# SCH_n2_power_distribution_board_v3_2022-.net
KiCad netlist of a schematic drawn in EasyEDA
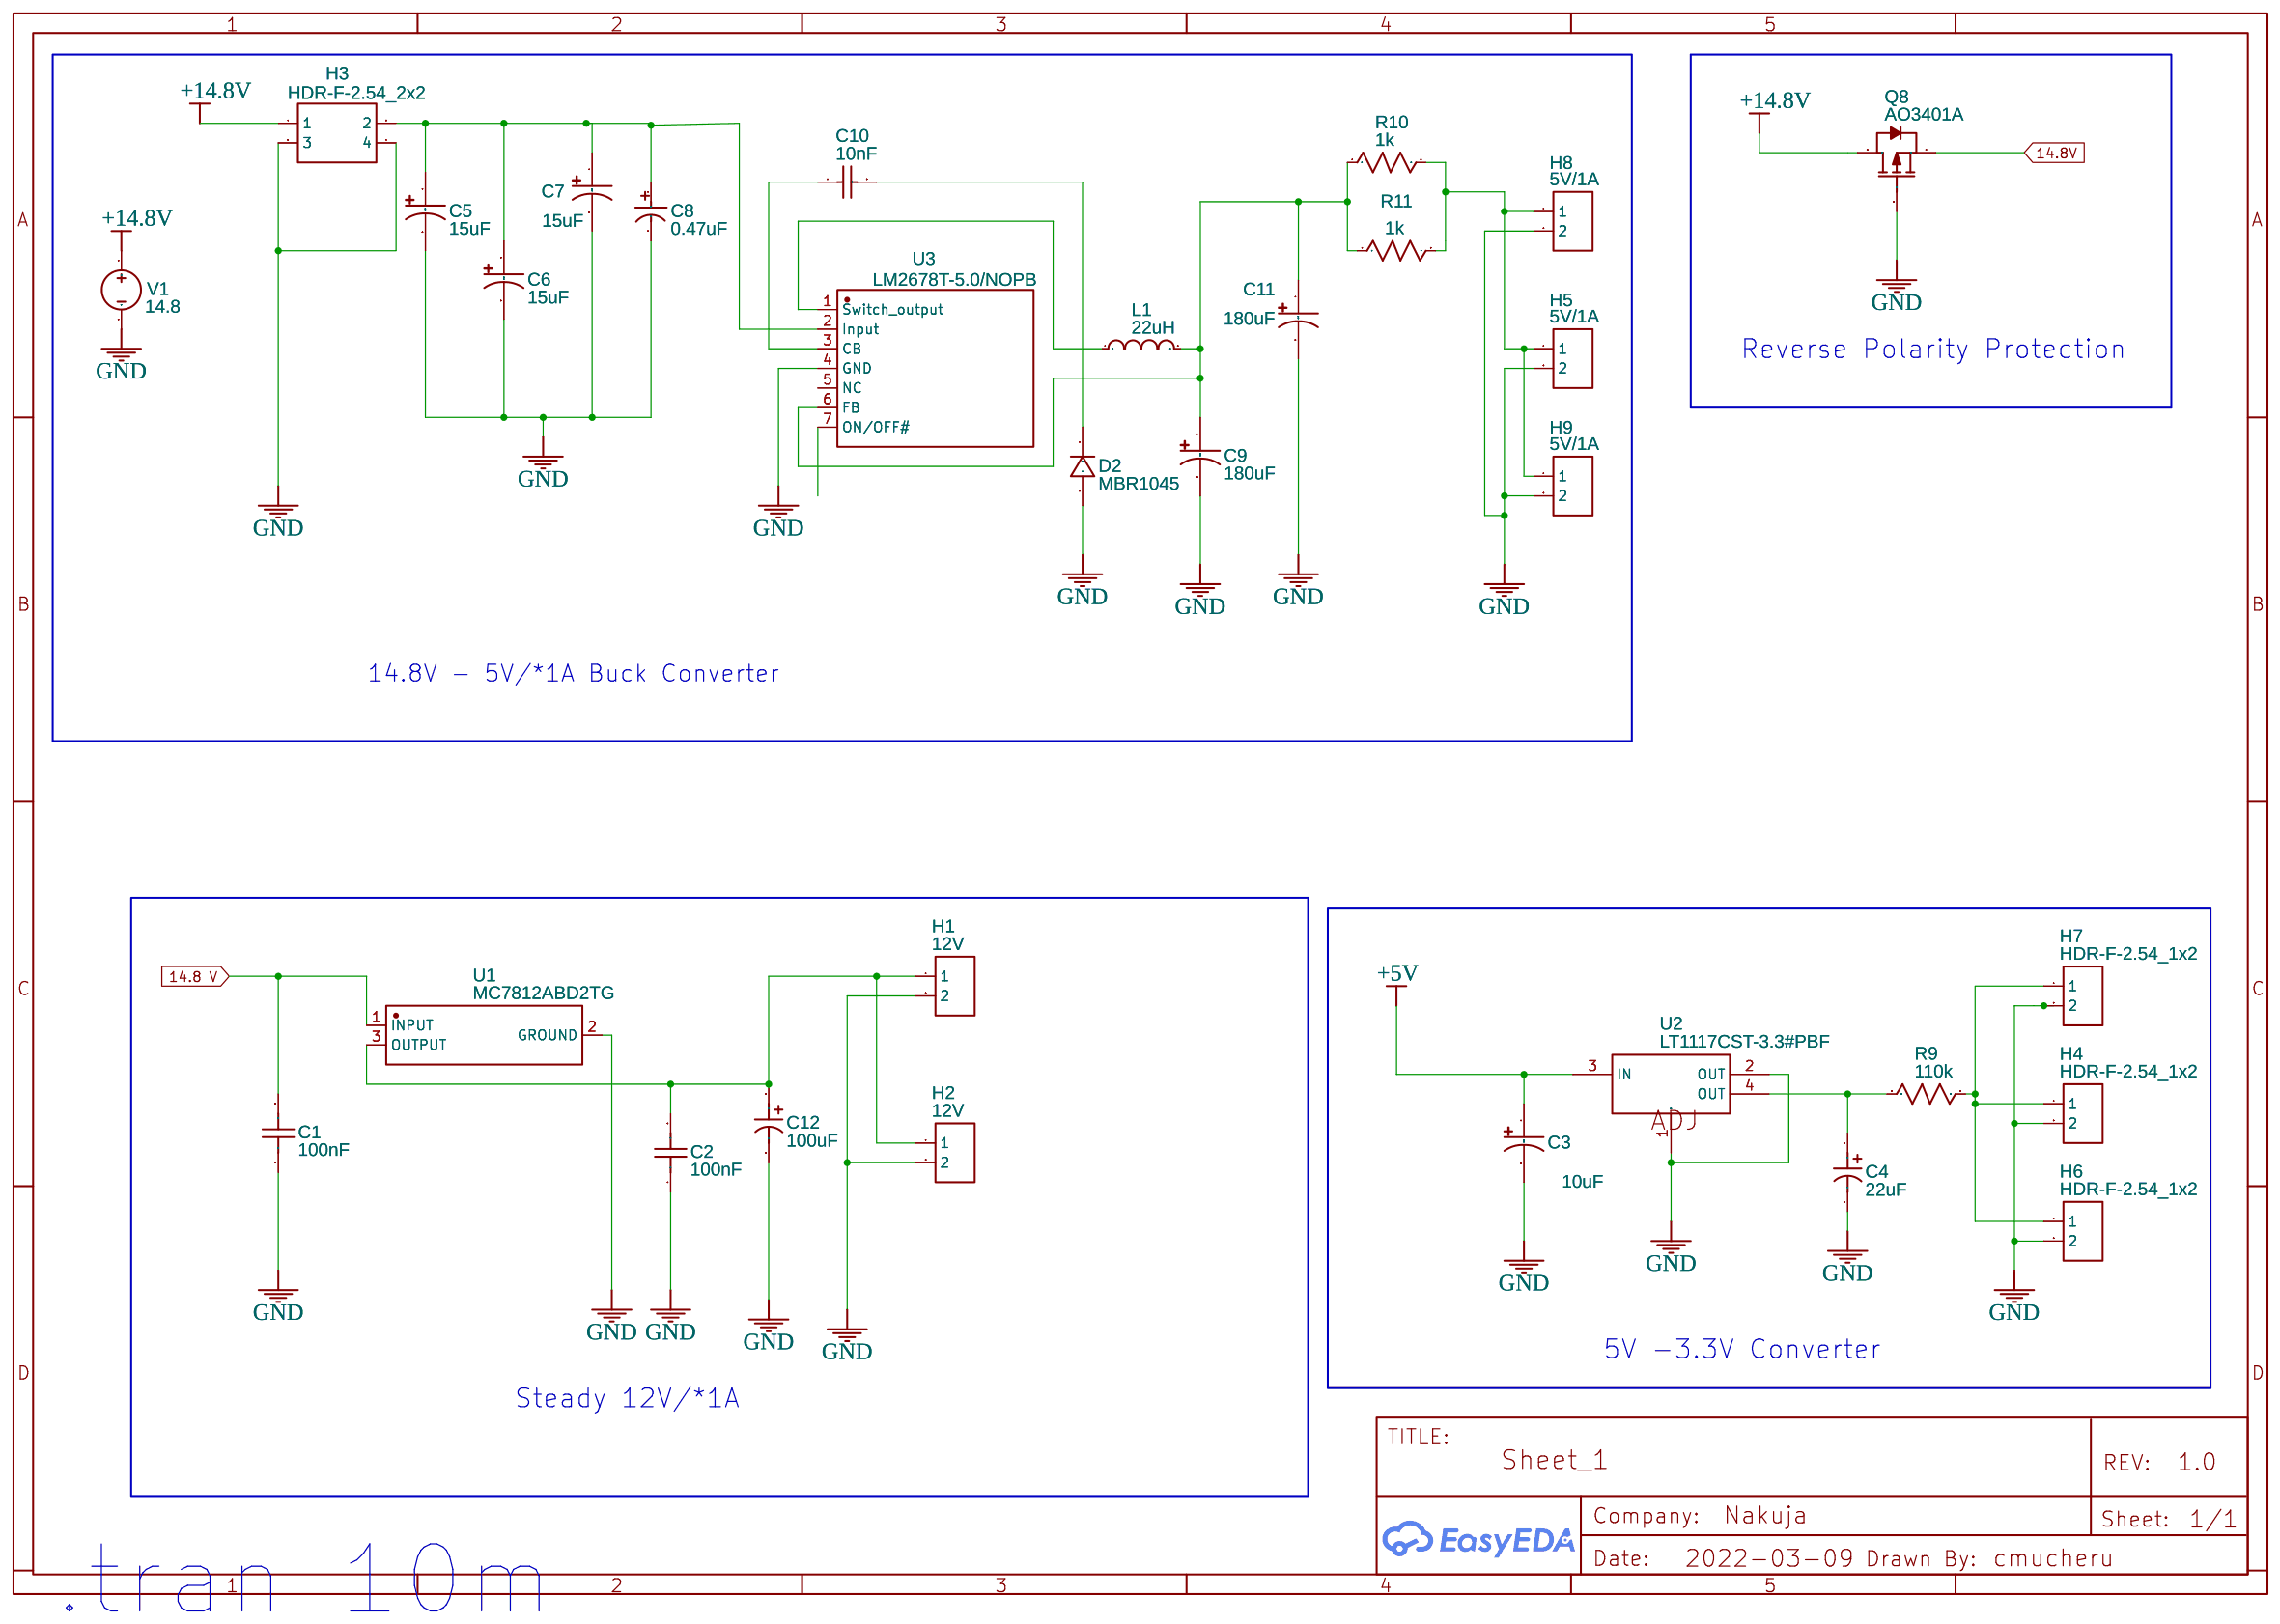
[diagram p0: schematic sheet]

(export (version "E")
  (design (tool "Eeschema 10.0.6"))
  (components
    (comp (ref "C1")
      (value "100nF")
      (fields
        (field (name "BOM_Manufacturer Part") "CC1H104ZA19D3F5P10MF")
        (field (name "BOM_Supplier Part") "C254086")
      )
      (libsource (lib "") (part "CC1H104ZA19D3F5P10MF"))
    )
    (comp (ref "C2")
      (value "100nF")
      (fields
        (field (name "BOM_Manufacturer Part") "CC1H104ZA19D3F5P10MF")
        (field (name "BOM_Supplier Part") "C254086")
      )
      (libsource (lib "") (part "CC1H104ZA19D3F5P10MF"))
    )
    (comp (ref "C3")
      (value "10uF")
      (fields
        (field (name "BOM_Manufacturer Part") "VE-100M1H0505-TRO")
        (field (name "BOM_Supplier Part") "C249452")
      )
      (libsource (lib "") (part "VE-100M1H0505-TRO"))
    )
    (comp (ref "C4")
      (value "22uF")
      (fields
        (field (name "BOM_Manufacturer Part") "RVT22UF50V67RV0028")
        (field (name "BOM_Supplier Part") "C2836438")
      )
      (libsource (lib "") (part "RVT22UF50V67RV0028"))
    )
    (comp (ref "C5")
      (value "15uF")
      (fields
        (field (name "BOM_Manufacturer Part") "UUD1H150MCL1GS")
        (field (name "BOM_Supplier Part") "C340748")
      )
      (libsource (lib "") (part "UUD1H150MCL1GS"))
    )
    (comp (ref "C6")
      (value "15uF")
      (fields
        (field (name "BOM_Manufacturer Part") "UUD1H150MCL1GS")
        (field (name "BOM_Supplier Part") "C340748")
      )
      (libsource (lib "") (part "UUD1H150MCL1GS"))
    )
    (comp (ref "C7")
      (value "15uF")
      (fields
        (field (name "BOM_Manufacturer Part") "UUD1H150MCL1GS")
        (field (name "BOM_Supplier Part") "C340748")
      )
      (libsource (lib "") (part "UUD1H150MCL1GS_1"))
    )
    (comp (ref "C8")
      (value "0.47uF")
      (fields
        (field (name "BOM_Manufacturer Part") "CS1HR47M-CRC54")
        (field (name "BOM_Supplier Part") "C117834")
      )
      (libsource (lib "") (part "CS1HR47M-CRC54"))
    )
    (comp (ref "C9")
      (value "180uF")
      (fields
        (field (name "BOM_Manufacturer Part") "VKMC1001C181MV")
        (field (name "BOM_Supplier Part") "C487303")
      )
      (libsource (lib "") (part "VKMC1001C181MV"))
    )
    (comp (ref "C10")
      (value "10nF")
      (fields
        (field (name "BOM_Manufacturer Part") "CL21B103KBANNNC")
        (field (name "BOM_Supplier Part") "C1710")
      )
      (libsource (lib "") (part "CL21B103KBANNNC"))
    )
    (comp (ref "C11")
      (value "180uF")
      (fields
        (field (name "BOM_Manufacturer Part") "VKMC1001C181MV")
        (field (name "BOM_Supplier Part") "C487303")
      )
      (libsource (lib "") (part "VKMC1001C181MV"))
    )
    (comp (ref "C12")
      (value "100uF")
      (fields
        (field (name "BOM_Manufacturer Part") "RVT100UF35V67RV0034")
        (field (name "BOM_Supplier Part") "C2836442")
      )
      (libsource (lib "") (part "RVT100UF35V67RV0034"))
    )
    (comp (ref "D2")
      (value "MBR1045")
      (fields (field (name "BOM_Supplier Part") "C260253"))
      (libsource (lib "") (part "MBR1045"))
    )
    (comp (ref "H1")
      (value "12V")
      (fields (field (name "BOM_Supplier Part") "C49661"))
      (libsource (lib "") (part "HDR-F-2.54_1x2"))
    )
    (comp (ref "H2")
      (value "12V")
      (fields (field (name "BOM_Supplier Part") "C49661"))
      (libsource (lib "") (part "HDR-F-2.54_1x2"))
    )
    (comp (ref "H3")
      (value "HDR-F-2.54_2x2")
      (fields (field (name "BOM_Supplier Part") "C239342"))
      (libsource (lib "") (part "HDR-F-2.54_2x2"))
    )
    (comp (ref "H4")
      (value "HDR-F-2.54_1x2")
      (fields (field (name "BOM_Supplier Part") "C49661"))
      (libsource (lib "") (part "HDR-F-2.54_1x2"))
    )
    (comp (ref "H5")
      (value "5V/1A")
      (fields (field (name "BOM_Supplier Part") "C49661"))
      (libsource (lib "") (part "HDR-F-2.54_1x2"))
    )
    (comp (ref "H6")
      (value "HDR-F-2.54_1x2")
      (fields (field (name "BOM_Supplier Part") "C49661"))
      (libsource (lib "") (part "HDR-F-2.54_1x2"))
    )
    (comp (ref "H7")
      (value "HDR-F-2.54_1x2")
      (fields (field (name "BOM_Supplier Part") "C49661"))
      (libsource (lib "") (part "HDR-F-2.54_1x2"))
    )
    (comp (ref "H8")
      (value "5V/1A")
      (fields (field (name "BOM_Supplier Part") "C49661"))
      (libsource (lib "") (part "HDR-F-2.54_1x2"))
    )
    (comp (ref "H9")
      (value "5V/1A")
      (fields (field (name "BOM_Supplier Part") "C49661"))
      (libsource (lib "") (part "HDR-F-2.54_1x2"))
    )
    (comp (ref "L1")
      (value "22uH")
      (fields
        (field (name "BOM_Manufacturer Part") "SLO0630H220MTT")
        (field (name "BOM_Supplier Part") "C207843")
      )
      (libsource (lib "") (part "SLO0630H220MTT"))
    )
    (comp (ref "Q8")
      (value "AO3401A")
      (fields (field (name "BOM_Supplier Part") "C15127"))
      (libsource (lib "") (part "AO3401A"))
    )
    (comp (ref "R9") (value "110k") (libsource (lib "") (part "R_0603_US")))
    (comp (ref "R10") (value "1k") (libsource (lib "") (part "R_0603_US")))
    (comp (ref "R11") (value "1k") (libsource (lib "") (part "R_0603_US")))
    (comp (ref "U1")
      (value "MC7812ABD2TG")
      (fields (field (name "BOM_Supplier Part") "C154818"))
      (libsource (lib "") (part "MC7812ABD2TG"))
    )
    (comp (ref "U2")
      (value "LT1117CST-3.3#PBF")
      (fields (field (name "BOM_Supplier Part") "C140395"))
      (libsource (lib "") (part "LT1117CST-3.3#PBF"))
    )
    (comp (ref "U3")
      (value "LM2678T-5.0/NOPB")
      (fields (field (name "BOM_Supplier Part") "C390086"))
      (libsource (lib "") (part "LM2678T-5.0/NOPB"))
    )
    (comp (ref "V1") (value "14.8") (libsource (lib "") (part "VDC")))
  )
  (nets
    (net (code "1") (name "+5V") (class "Default")
      (node (ref "C3") (pin "1") (pinfunction "1_1") (pintype "unspecified"))
      (node (ref "U2") (pin "3") (pinfunction "IN_3") (pintype "passive"))
    )
    (net (code "2") (name "+14.8V") (class "Default")
      (node (ref "H3") (pin "1") (pinfunction "1_1") (pintype "unspecified"))
      (node (ref "Q8") (pin "3") (pinfunction "D_3") (pintype "unspecified"))
      (node (ref "V1") (pin "1") (pinfunction "1_1") (pintype "unspecified"))
    )
    (net (code "3") (name "14.8 V") (class "Default")
      (node (ref "C1") (pin "2") (pinfunction "2_2") (pintype "unspecified"))
      (node (ref "U1") (pin "1") (pinfunction "INPUT_1") (pintype "unspecified"))
    )
    (net (code "4") (name "14.8V") (class "Default")
      (node (ref "Q8") (pin "2") (pinfunction "S_2") (pintype "unspecified"))
    )
    (net (code "5") (name "GND") (class "Default")
      (node (ref "C1") (pin "1") (pinfunction "1_1") (pintype "unspecified"))
      (node (ref "C11") (pin "2") (pinfunction "2_2") (pintype "unspecified"))
      (node (ref "C12") (pin "2") (pinfunction "2_2") (pintype "input"))
      (node (ref "C2") (pin "1") (pinfunction "1_1") (pintype "unspecified"))
      (node (ref "C3") (pin "2") (pinfunction "2_2") (pintype "unspecified"))
      (node (ref "C4") (pin "2") (pinfunction "2_2") (pintype "input"))
      (node (ref "C5") (pin "2") (pinfunction "2_2") (pintype "unspecified"))
      (node (ref "C6") (pin "2") (pinfunction "2_2") (pintype "unspecified"))
      (node (ref "C7") (pin "2") (pinfunction "2_2") (pintype "unspecified"))
      (node (ref "C8") (pin "2") (pinfunction "2_2") (pintype "input"))
      (node (ref "C9") (pin "2") (pinfunction "2_2") (pintype "unspecified"))
      (node (ref "D2") (pin "2") (pinfunction "A_2") (pintype "unspecified"))
      (node (ref "H1") (pin "2") (pinfunction "2_2") (pintype "input"))
      (node (ref "H2") (pin "2") (pinfunction "2_2") (pintype "input"))
      (node (ref "H3") (pin "3") (pinfunction "3_3") (pintype "unspecified"))
      (node (ref "H3") (pin "4") (pinfunction "4_4") (pintype "unspecified"))
      (node (ref "H4") (pin "2") (pinfunction "2_2") (pintype "input"))
      (node (ref "H5") (pin "2") (pinfunction "2_2") (pintype "input"))
      (node (ref "H6") (pin "2") (pinfunction "2_2") (pintype "input"))
      (node (ref "H7") (pin "2") (pinfunction "2_2") (pintype "input"))
      (node (ref "H8") (pin "2") (pinfunction "2_2") (pintype "input"))
      (node (ref "H9") (pin "2") (pinfunction "2_2") (pintype "input"))
      (node (ref "Q8") (pin "1") (pinfunction "G_1") (pintype "unspecified"))
      (node (ref "U1") (pin "2") (pinfunction "GROUND_2") (pintype "unspecified"))
      (node (ref "U2") (pin "1") (pinfunction "ADJ_1") (pintype "passive"))
      (node (ref "U2") (pin "2") (pinfunction "OUT_2") (pintype "passive"))
      (node (ref "U3") (pin "4") (pinfunction "GND_4") (pintype "unspecified"))
      (node (ref "V1") (pin "2") (pinfunction "2_2") (pintype "unspecified"))
    )
    (net (code "6") (name "Net-(C4-Pad1)") (class "Default")
      (node (ref "C4") (pin "1") (pinfunction "1_1") (pintype "input"))
      (node (ref "R9") (pin "1") (pinfunction "1_1") (pintype "unspecified"))
      (node (ref "U2") (pin "4") (pinfunction "OUT_4") (pintype "passive"))
    )
    (net (code "7") (name "Net-(D2-C)") (class "Default")
      (node (ref "C10") (pin "2") (pinfunction "2_2") (pintype "input"))
      (node (ref "D2") (pin "1") (pinfunction "C_1") (pintype "unspecified"))
    )
    (net (code "8") (name "Net-(H4-Pad1)") (class "Default")
      (node (ref "H4") (pin "1") (pinfunction "1_1") (pintype "input"))
      (node (ref "H6") (pin "1") (pinfunction "1_1") (pintype "input"))
      (node (ref "H7") (pin "1") (pinfunction "1_1") (pintype "input"))
      (node (ref "R9") (pin "2") (pinfunction "2_2") (pintype "unspecified"))
    )
    (net (code "9") (name "Net-(H5-Pad1)") (class "Default")
      (node (ref "H5") (pin "1") (pinfunction "1_1") (pintype "input"))
      (node (ref "H8") (pin "1") (pinfunction "1_1") (pintype "input"))
      (node (ref "H9") (pin "1") (pinfunction "1_1") (pintype "input"))
      (node (ref "R10") (pin "2") (pinfunction "2_2") (pintype "unspecified"))
      (node (ref "R11") (pin "2") (pinfunction "2_2") (pintype "unspecified"))
    )
    (net (code "10") (name "Net-(U1-OUTPUT)") (class "Default")
      (node (ref "C12") (pin "1") (pinfunction "1_1") (pintype "input"))
      (node (ref "C2") (pin "2") (pinfunction "2_2") (pintype "unspecified"))
      (node (ref "H1") (pin "1") (pinfunction "1_1") (pintype "input"))
      (node (ref "H2") (pin "1") (pinfunction "1_1") (pintype "input"))
      (node (ref "U1") (pin "3") (pinfunction "OUTPUT_3") (pintype "unspecified"))
    )
    (net (code "11") (name "Net-(U3-CB)") (class "Default")
      (node (ref "C10") (pin "1") (pinfunction "1_1") (pintype "input"))
      (node (ref "U3") (pin "3") (pinfunction "CB_3") (pintype "unspecified"))
    )
    (net (code "12") (name "Net-(U3-FB)") (class "Default")
      (node (ref "C11") (pin "1") (pinfunction "1_1") (pintype "unspecified"))
      (node (ref "C9") (pin "1") (pinfunction "1_1") (pintype "unspecified"))
      (node (ref "L1") (pin "2") (pinfunction "2_2") (pintype "unspecified"))
      (node (ref "R10") (pin "1") (pinfunction "1_1") (pintype "unspecified"))
      (node (ref "R11") (pin "1") (pinfunction "1_1") (pintype "unspecified"))
      (node (ref "U3") (pin "6") (pinfunction "FB_6") (pintype "unspecified"))
    )
    (net (code "13") (name "Net-(U3-Input)") (class "Default")
      (node (ref "C5") (pin "1") (pinfunction "1_1") (pintype "unspecified"))
      (node (ref "C6") (pin "1") (pinfunction "1_1") (pintype "unspecified"))
      (node (ref "C7") (pin "1") (pinfunction "1_1") (pintype "unspecified"))
      (node (ref "C8") (pin "1") (pinfunction "1_1") (pintype "input"))
      (node (ref "H3") (pin "2") (pinfunction "2_2") (pintype "unspecified"))
      (node (ref "U3") (pin "2") (pinfunction "Input_2") (pintype "unspecified"))
    )
    (net (code "14") (name "Net-(U3-Switch_output)") (class "Default")
      (node (ref "L1") (pin "1") (pinfunction "1_1") (pintype "unspecified"))
      (node (ref "U3") (pin "1") (pinfunction "Switch_output_1") (pintype "unspecified"))
    )
    (net (code "15") (name "unconnected-(U3-NC-Pad5)") (class "Default")
      (node (ref "U3") (pin "5") (pinfunction "NC_5") (pintype "unspecified"))
    )
    (net (code "16") (name "unconnected-(U3-ON{slash}OFF#-Pad7)") (class "Default")
      (node (ref "U3") (pin "7") (pinfunction "ON/OFF#_7") (pintype "unspecified"))
    )
  )
)
